# main.net
KiCad netlist of a schematic drawn in Altium Designer
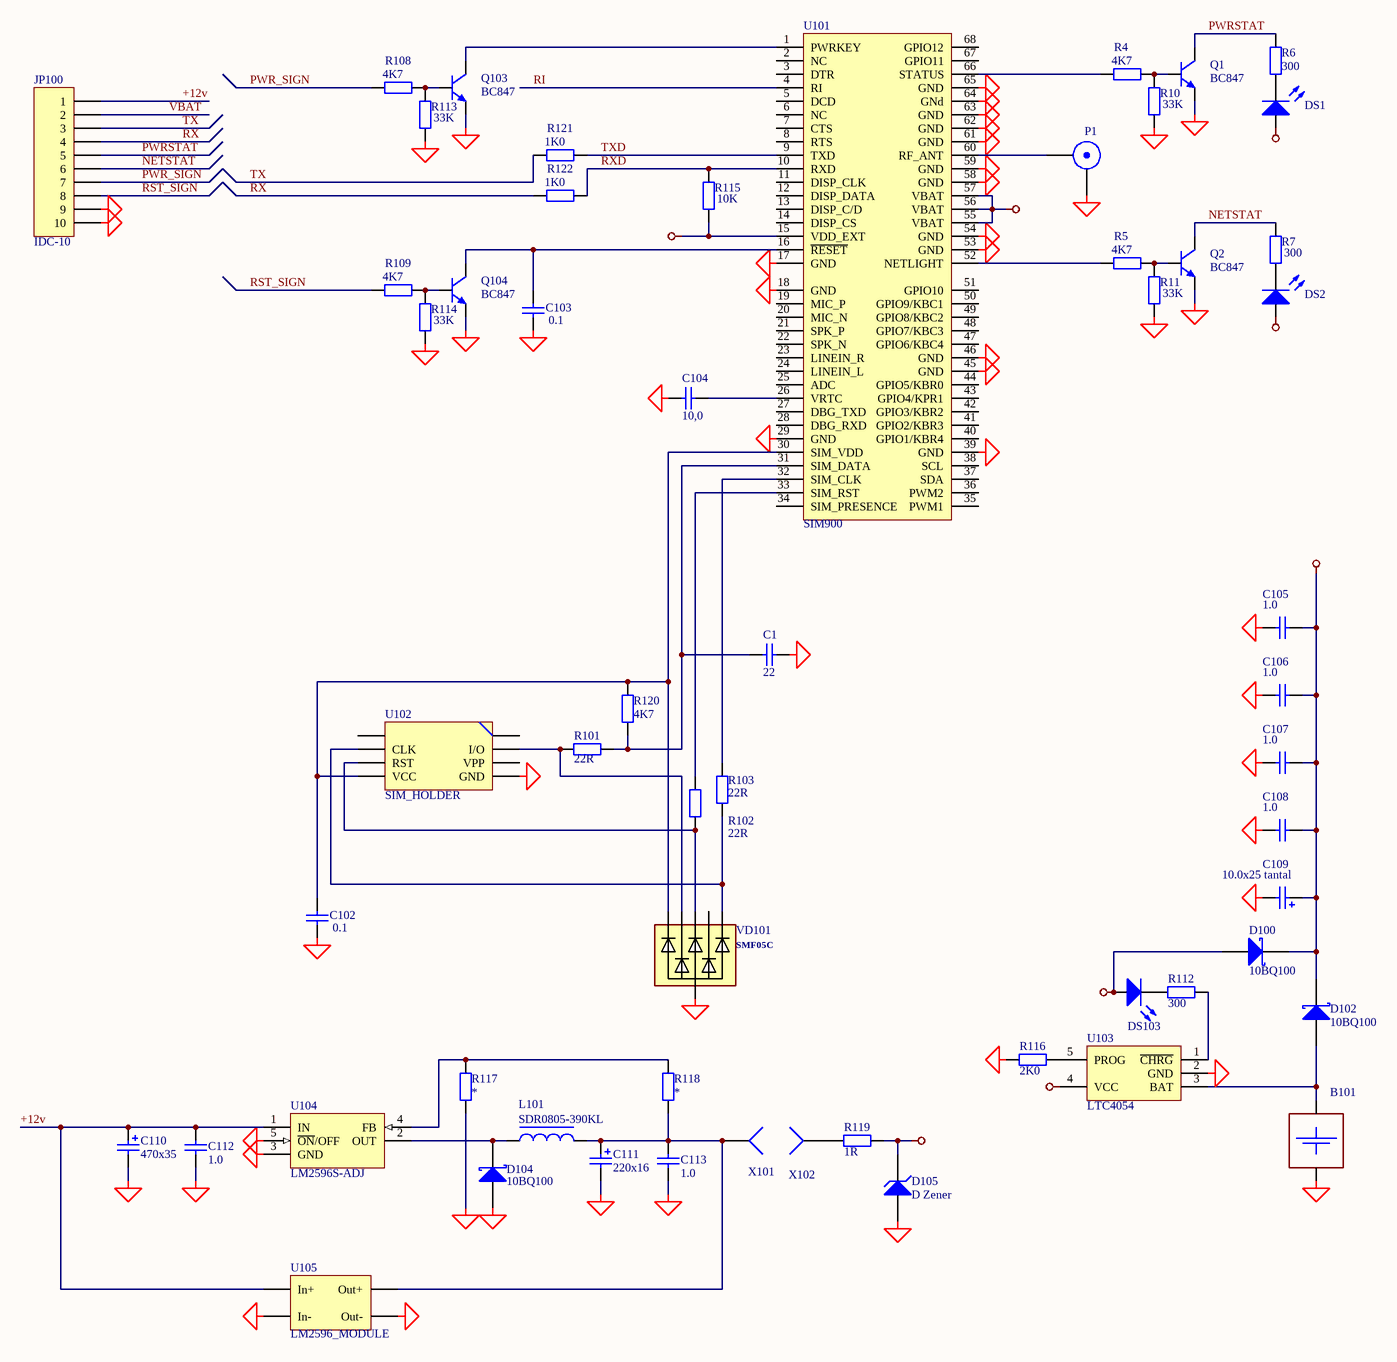
[diagram p0: main.SchDoc]

(export (version "E")
  (design (tool "Eeschema 10.0.6"))
  (components
    (comp (ref "B101")
      (value "BAT18650_HOLDER")
      (footprint "BAT18650_HOLDER")
      (libsource (lib "PAL") (part "BAT18650_HOLDER"))
    )
    (comp (ref "C1")
      (value "22")
      (footprint "_1206")
      (description "Capacitor")
      (fields (field (name "MANUFACTURER") "Generic Components") (field (name "PUBLISHER") "Altium Limited"))
      (libsource (lib "Miscellaneous Devices") (part "Cap Semi"))
    )
    (comp (ref "C102")
      (value "0.1")
      (footprint "_1206")
      (description "Capacitor")
      (fields (field (name "MANUFACTURER") "Generic Components") (field (name "PUBLISHER") "Altium Limited"))
      (libsource (lib "Miscellaneous Devices") (part "Cap Semi"))
    )
    (comp (ref "C103")
      (value "0.1")
      (footprint "_1206")
      (description "Capacitor")
      (fields (field (name "MANUFACTURER") "Generic Components") (field (name "PUBLISHER") "Altium Limited"))
      (libsource (lib "Miscellaneous Devices") (part "Cap Semi"))
    )
    (comp (ref "C104")
      (value "10,0")
      (footprint "_1206")
      (description "Capacitor")
      (fields (field (name "MANUFACTURER") "Generic Components") (field (name "PUBLISHER") "Altium Limited"))
      (libsource (lib "Miscellaneous Devices") (part "Cap Semi"))
    )
    (comp (ref "C105")
      (value "1.0")
      (footprint "_1206")
      (description "Capacitor")
      (fields (field (name "MANUFACTURER") "Generic Components") (field (name "PUBLISHER") "Altium Limited"))
      (libsource (lib "Miscellaneous Devices") (part "Cap Semi"))
    )
    (comp (ref "C106")
      (value "1.0")
      (footprint "_1206")
      (description "Capacitor")
      (fields (field (name "MANUFACTURER") "Generic Components") (field (name "PUBLISHER") "Altium Limited"))
      (libsource (lib "Miscellaneous Devices") (part "Cap Semi"))
    )
    (comp (ref "C107")
      (value "1.0")
      (footprint "_1206")
      (description "Capacitor")
      (fields (field (name "MANUFACTURER") "Generic Components") (field (name "PUBLISHER") "Altium Limited"))
      (libsource (lib "Miscellaneous Devices") (part "Cap Semi"))
    )
    (comp (ref "C108")
      (value "1.0")
      (footprint "_1206")
      (description "Capacitor")
      (fields (field (name "MANUFACTURER") "Generic Components") (field (name "PUBLISHER") "Altium Limited"))
      (libsource (lib "Miscellaneous Devices") (part "Cap Semi"))
    )
    (comp (ref "C109")
      (value "10.0x25 tantal")
      (footprint "CAP_EL_6_3")
      (description "Polarized Capacitor (Radial)")
      (fields (field (name "MANUFACTURER") "Generic Components") (field (name "PUBLISHER") "Altium Limited"))
      (libsource (lib "PAL") (part "Cap Pol1"))
    )
    (comp (ref "C110")
      (value "470x35")
      (footprint "el5")
      (description "Polarized Capacitor (Radial)")
      (fields (field (name "MANUFACTURER") "Generic Components") (field (name "PUBLISHER") "Altium Limited"))
      (libsource (lib "BUF") (part "Cap Pol"))
    )
    (comp (ref "C111")
      (value "220x16")
      (footprint "el3")
      (description "Polarized Capacitor (Radial)")
      (fields (field (name "MANUFACTURER") "Generic Components") (field (name "PUBLISHER") "Altium Limited"))
      (libsource (lib "BUF") (part "Cap Pol"))
    )
    (comp (ref "C112")
      (value "Cap")
      (footprint "_1206")
      (description "Capacitor")
      (fields
        (field (name "MANUFACTURER") "Generic Components")
        (field (name "ALTIUM_VALUE") "1.0")
        (field (name "PUBLISHER") "Altium Limited")
      )
      (libsource (lib "BUF") (part "Cap"))
    )
    (comp (ref "C113")
      (value "Cap")
      (footprint "_1206")
      (description "Capacitor")
      (fields
        (field (name "MANUFACTURER") "Generic Components")
        (field (name "ALTIUM_VALUE") "1.0")
        (field (name "PUBLISHER") "Altium Limited")
      )
      (libsource (lib "BUF") (part "Cap"))
    )
    (comp (ref "D100")
      (value "10BQ100")
      (footprint "DSO-C2/X2.3")
      (description "Schottky Rectifier")
      (fields
        (field (name "MANUFACTURER") "International Rectifier")
        (field (name "PUBLISHER") "Altium Limited")
      )
      (libsource (lib "IR Discrete Diode") (part "10BQ015"))
    )
    (comp (ref "D102")
      (value "10BQ100")
      (footprint "DSO-C2/X2.3")
      (description "Schottky Rectifier")
      (fields
        (field (name "MANUFACTURER") "International Rectifier")
        (field (name "PUBLISHER") "Altium Limited")
      )
      (libsource (lib "IR Discrete Diode") (part "10BQ015"))
    )
    (comp (ref "D104")
      (value "10BQ100")
      (footprint "DSO-C2/X2.3")
      (description "Schottky Rectifier")
      (fields
        (field (name "MANUFACTURER") "International Rectifier")
        (field (name "PUBLISHER") "Altium Limited")
      )
      (libsource (lib "IR Discrete Diode") (part "10BQ015"))
    )
    (comp (ref "D105")
      (value "D Zener")
      (footprint "_1206d")
      (description "Zener Diode")
      (fields (field (name "MANUFACTURER") "Generic Components") (field (name "PUBLISHER") "Altium Limited"))
      (libsource (lib "Miscellaneous Devices") (part "D Zener"))
    )
    (comp (ref "DS1")
      (value "LED0")
      (footprint "el3")
      (description "Typical INFRARED GaAs LED")
      (fields (field (name "MANUFACTURER") "Generic Components") (field (name "PUBLISHER") "Altium Limited"))
      (libsource (lib "PAL") (part "LED0"))
    )
    (comp (ref "DS2")
      (value "LED0")
      (footprint "el3")
      (description "Typical INFRARED GaAs LED")
      (fields (field (name "MANUFACTURER") "Generic Components") (field (name "PUBLISHER") "Altium Limited"))
      (libsource (lib "PAL") (part "LED0"))
    )
    (comp (ref "DS103")
      (value "LED0")
      (footprint "el3")
      (description "Typical INFRARED GaAs LED")
      (fields (field (name "MANUFACTURER") "Generic Components") (field (name "PUBLISHER") "Altium Limited"))
      (libsource (lib "") (part "LED0_1"))
    )
    (comp (ref "JP100")
      (value "IDC-10")
      (footprint "HDR2X5")
      (description "Header, 10-Pin")
      (fields (field (name "MANUFACTURER") "Generic Components") (field (name "PUBLISHER") "Altium Limited"))
      (libsource (lib "Miscellaneous Connectors") (part "Header 10"))
    )
    (comp (ref "L101")
      (value "SDR0805-390KL")
      (footprint "L10x10")
      (description "Magnetic-Core Inductor")
      (fields (field (name "MANUFACTURER") "Generic Components") (field (name "PUBLISHER") "Altium Limited"))
      (libsource (lib "PAL") (part "Inductor Konstr 2"))
    )
    (comp (ref "P1")
      (value "SMB")
      (footprint "SMB_V-RJ45")
      (description "SMB Straight Connector")
      (fields (field (name "MANUFACTURER") "Generic Components") (field (name "PUBLISHER") "Altium Limited"))
      (libsource (lib "Miscellaneous Connectors") (part "SMB"))
    )
    (comp (ref "Q1")
      (value "BC847")
      (footprint "SO-G3/C2.5")
      (description "General Purpose Transistor NPN Silicon")
      (fields (field (name "MANUFACTURER") "Motorola") (field (name "PUBLISHER") "Altium Limited"))
      (libsource (lib "PAL") (part "BC847ALT1"))
    )
    (comp (ref "Q2")
      (value "BC847")
      (footprint "SO-G3/C2.5")
      (description "General Purpose Transistor NPN Silicon")
      (fields (field (name "MANUFACTURER") "Motorola") (field (name "PUBLISHER") "Altium Limited"))
      (libsource (lib "PAL") (part "BC847ALT1"))
    )
    (comp (ref "Q103")
      (value "BC847")
      (footprint "SO-G3/C2.5")
      (description "General Purpose Transistor NPN Silicon")
      (fields (field (name "MANUFACTURER") "Motorola") (field (name "PUBLISHER") "Altium Limited"))
      (libsource (lib "PAL") (part "BC847ALT1"))
    )
    (comp (ref "Q104")
      (value "BC847")
      (footprint "SO-G3/C2.5")
      (description "General Purpose Transistor NPN Silicon")
      (fields (field (name "MANUFACTURER") "Motorola") (field (name "PUBLISHER") "Altium Limited"))
      (libsource (lib "PAL") (part "BC847ALT1"))
    )
    (comp (ref "R4")
      (value "4K7")
      (footprint "_1206")
      (description "Resistor")
      (fields (field (name "MANUFACTURER") "Generic Components") (field (name "PUBLISHER") "Altium Limited"))
      (libsource (lib "Miscellaneous Devices") (part "Res2"))
    )
    (comp (ref "R5")
      (value "4K7")
      (footprint "_1206")
      (description "Resistor")
      (fields (field (name "MANUFACTURER") "Generic Components") (field (name "PUBLISHER") "Altium Limited"))
      (libsource (lib "Miscellaneous Devices") (part "Res2"))
    )
    (comp (ref "R6")
      (value "300")
      (footprint "_1206")
      (description "Resistor")
      (fields (field (name "MANUFACTURER") "Generic Components") (field (name "PUBLISHER") "Altium Limited"))
      (libsource (lib "") (part "Res2_3"))
    )
    (comp (ref "R7")
      (value "300")
      (footprint "_1206")
      (description "Resistor")
      (fields (field (name "MANUFACTURER") "Generic Components") (field (name "PUBLISHER") "Altium Limited"))
      (libsource (lib "") (part "Res2_2"))
    )
    (comp (ref "R10")
      (value "33K")
      (footprint "_1206")
      (description "Resistor")
      (fields (field (name "MANUFACTURER") "Generic Components") (field (name "PUBLISHER") "Altium Limited"))
      (libsource (lib "") (part "Res2_2"))
    )
    (comp (ref "R11")
      (value "33K")
      (footprint "_1206")
      (description "Resistor")
      (fields (field (name "MANUFACTURER") "Generic Components") (field (name "PUBLISHER") "Altium Limited"))
      (libsource (lib "") (part "Res2_2"))
    )
    (comp (ref "R101")
      (value "22R")
      (footprint "_1206")
      (description "Resistor")
      (fields (field (name "MANUFACTURER") "Generic Components") (field (name "PUBLISHER") "Altium Limited"))
      (libsource (lib "") (part "Res2_2"))
    )
    (comp (ref "R102")
      (value "22R")
      (footprint "_1206")
      (description "Resistor")
      (fields (field (name "MANUFACTURER") "Generic Components") (field (name "PUBLISHER") "Altium Limited"))
      (libsource (lib "Miscellaneous Devices") (part "Res2"))
    )
    (comp (ref "R103")
      (value "22R")
      (footprint "_1206")
      (description "Resistor")
      (fields (field (name "MANUFACTURER") "Generic Components") (field (name "PUBLISHER") "Altium Limited"))
      (libsource (lib "Miscellaneous Devices") (part "Res2"))
    )
    (comp (ref "R108")
      (value "4K7")
      (footprint "_1206")
      (description "Resistor")
      (fields (field (name "MANUFACTURER") "Generic Components") (field (name "PUBLISHER") "Altium Limited"))
      (libsource (lib "Miscellaneous Devices") (part "Res2"))
    )
    (comp (ref "R109")
      (value "4K7")
      (footprint "_1206")
      (description "Resistor")
      (fields (field (name "MANUFACTURER") "Generic Components") (field (name "PUBLISHER") "Altium Limited"))
      (libsource (lib "Miscellaneous Devices") (part "Res2"))
    )
    (comp (ref "R112")
      (value "300")
      (footprint "_1206")
      (description "Resistor")
      (fields (field (name "MANUFACTURER") "Generic Components") (field (name "PUBLISHER") "Altium Limited"))
      (libsource (lib "") (part "Res2_1"))
    )
    (comp (ref "R113")
      (value "33K")
      (footprint "_1206")
      (description "Resistor")
      (fields (field (name "MANUFACTURER") "Generic Components") (field (name "PUBLISHER") "Altium Limited"))
      (libsource (lib "") (part "Res2_2"))
    )
    (comp (ref "R114")
      (value "33K")
      (footprint "_1206")
      (description "Resistor")
      (fields (field (name "MANUFACTURER") "Generic Components") (field (name "PUBLISHER") "Altium Limited"))
      (libsource (lib "") (part "Res2_2"))
    )
    (comp (ref "R115")
      (value "10K")
      (footprint "_1206")
      (description "Resistor")
      (fields (field (name "MANUFACTURER") "Generic Components") (field (name "PUBLISHER") "Altium Limited"))
      (libsource (lib "") (part "Res2_2"))
    )
    (comp (ref "R116")
      (value "2K0")
      (footprint "_1206")
      (description "Resistor")
      (fields (field (name "MANUFACTURER") "Generic Components") (field (name "PUBLISHER") "Altium Limited"))
      (libsource (lib "") (part "Res2_1"))
    )
    (comp (ref "R117")
      (value "*")
      (footprint "_1206")
      (description "Resistor")
      (fields (field (name "MANUFACTURER") "Generic Components") (field (name "PUBLISHER") "Altium Limited"))
      (libsource (lib "Miscellaneous Devices") (part "Res2"))
    )
    (comp (ref "R118")
      (value "*")
      (footprint "_1206")
      (description "Resistor")
      (fields (field (name "MANUFACTURER") "Generic Components") (field (name "PUBLISHER") "Altium Limited"))
      (libsource (lib "Miscellaneous Devices") (part "Res2"))
    )
    (comp (ref "R119")
      (value "1R")
      (footprint "_1206")
      (description "Resistor")
      (fields (field (name "MANUFACTURER") "Generic Components") (field (name "PUBLISHER") "Altium Limited"))
      (libsource (lib "") (part "Res2_3"))
    )
    (comp (ref "R120")
      (value "4K7")
      (footprint "_1206")
      (description "Resistor")
      (fields (field (name "MANUFACTURER") "Generic Components") (field (name "PUBLISHER") "Altium Limited"))
      (libsource (lib "Miscellaneous Devices") (part "Res2"))
    )
    (comp (ref "R121")
      (value "1K0")
      (footprint "_1206")
      (description "Resistor")
      (fields (field (name "MANUFACTURER") "Generic Components") (field (name "PUBLISHER") "Altium Limited"))
      (libsource (lib "Miscellaneous Devices") (part "Res2"))
    )
    (comp (ref "R122")
      (value "1K0")
      (footprint "_1206")
      (description "Resistor")
      (fields (field (name "MANUFACTURER") "Generic Components") (field (name "PUBLISHER") "Altium Limited"))
      (libsource (lib "Miscellaneous Devices") (part "Res2"))
    )
    (comp (ref "U101") (value "SIM900") (footprint "SIM900F") (libsource (lib "Schlib1") (part "SIM900")))
    (comp (ref "U102")
      (value "SIM_HOLDER")
      (footprint "SIM_HOLDER_1")
      (libsource (lib "Schlib1") (part "SIM_HOLDER"))
    )
    (comp (ref "U103") (value "LTC4054") (footprint "SO-G5/P.95") (libsource (lib "PAL") (part "LTC4054")))
    (comp (ref "U104")
      (value "LM2596S-ADJ")
      (footprint "SIP-G5/Y2.1")
      (description "Simple Switcher Power Converter 150 kHz 3A Step Down Voltage Regulator")
      (fields
        (field (name "MANUFACTURER") "National Semiconductor")
        (field (name "PUBLISHER") "Altium Limited")
      )
      (libsource (lib "NSC Power Mgt Switching Regulator") (part "LM2596S-ADJ"))
    )
    (comp (ref "U105")
      (value "LM2596_MODULE")
      (footprint "LM2596_MODULE_1")
      (libsource (lib "PAL") (part "LM2596_MODULE"))
    )
    (comp (ref "VD101")
      (value "*")
      (footprint "sot363")
      (fields (field (name "MANUFACTURERPARTNUMBER") "SMF05C"))
      (libsource (lib "PAL") (part "SMF05C"))
    )
    (comp (ref "X101")
      (value "Socket")
      (footprint "PIN1")
      (fields (field (name "MANUFACTURER") "Generic Components") (field (name "PUBLISHER") "Altium Limited"))
      (libsource (lib "Miscellaneous Connectors") (part "Socket"))
    )
    (comp (ref "X102")
      (value "Socket")
      (footprint "PIN1")
      (fields (field (name "MANUFACTURER") "Generic Components") (field (name "PUBLISHER") "Altium Limited"))
      (libsource (lib "Miscellaneous Connectors") (part "Socket"))
    )
  )
  (nets
    (net (code "1") (name "+5v") (class "Default")
      (node (ref "D100") (pin "1") (pinfunction "A_1") (pintype "passive"))
      (node (ref "D105") (pin "2") (pinfunction "K_2") (pintype "passive"))
      (node (ref "DS103") (pin "1") (pinfunction "A_1") (pintype "passive"))
      (node (ref "R119") (pin "2") (pinfunction "2_2") (pintype "passive"))
      (node (ref "U103") (pin "4") (pinfunction "VCC_4") (pintype "passive"))
    )
    (net (code "2") (name "/+12v") (class "Default")
      (node (ref "C110") (pin "1") (pinfunction "1_1") (pintype "passive"))
      (node (ref "C112") (pin "2") (pinfunction "2_2") (pintype "passive"))
      (node (ref "JP100") (pin "1") (pinfunction "1_1") (pintype "passive"))
      (node (ref "U104") (pin "1") (pinfunction "IN_1") (pintype "power_in"))
      (node (ref "U105") (pin "1") (pinfunction "In+_1") (pintype "passive"))
    )
    (net (code "3") (name "/NETSTAT") (class "Default")
      (node (ref "JP100") (pin "6") (pinfunction "6_6") (pintype "passive"))
      (node (ref "Q2") (pin "3") (pinfunction "C_3") (pintype "passive"))
      (node (ref "R7") (pin "1") (pinfunction "1_1") (pintype "passive"))
    )
    (net (code "4") (name "/PWRSTAT") (class "Default")
      (node (ref "JP100") (pin "5") (pinfunction "5_5") (pintype "passive"))
      (node (ref "Q1") (pin "3") (pinfunction "C_3") (pintype "passive"))
      (node (ref "R6") (pin "2") (pinfunction "2_2") (pintype "passive"))
    )
    (net (code "5") (name "/PWR_SIGN") (class "Default")
      (node (ref "JP100") (pin "7") (pinfunction "7_7") (pintype "passive"))
      (node (ref "R108") (pin "2") (pinfunction "2_2") (pintype "passive"))
    )
    (net (code "6") (name "/RI") (class "Default")
      (node (ref "U101") (pin "4") (pinfunction "RI_4") (pintype "passive"))
    )
    (net (code "7") (name "/RST_SIGN") (class "Default")
      (node (ref "JP100") (pin "8") (pinfunction "8_8") (pintype "passive"))
      (node (ref "R109") (pin "2") (pinfunction "2_2") (pintype "passive"))
    )
    (net (code "8") (name "/RX") (class "Default")
      (node (ref "JP100") (pin "4") (pinfunction "4_4") (pintype "passive"))
      (node (ref "R122") (pin "2") (pinfunction "2_2") (pintype "passive"))
    )
    (net (code "9") (name "/RXD") (class "Default")
      (node (ref "R115") (pin "1") (pinfunction "1_1") (pintype "passive"))
      (node (ref "R122") (pin "1") (pinfunction "1_1") (pintype "passive"))
      (node (ref "U101") (pin "10") (pinfunction "RXD_10") (pintype "passive"))
    )
    (net (code "10") (name "/TX") (class "Default")
      (node (ref "JP100") (pin "3") (pinfunction "3_3") (pintype "passive"))
      (node (ref "R121") (pin "2") (pinfunction "2_2") (pintype "passive"))
    )
    (net (code "11") (name "/TXD") (class "Default")
      (node (ref "R121") (pin "1") (pinfunction "1_1") (pintype "passive"))
      (node (ref "U101") (pin "9") (pinfunction "TXD_9") (pintype "passive"))
    )
    (net (code "12") (name "GND") (class "Default")
      (node (ref "B101") (pin "2") (pinfunction "-_2") (pintype "passive"))
      (node (ref "C1") (pin "1") (pinfunction "1_1") (pintype "passive"))
      (node (ref "C102") (pin "1") (pinfunction "1_1") (pintype "passive"))
      (node (ref "C103") (pin "1") (pinfunction "1_1") (pintype "passive"))
      (node (ref "C104") (pin "2") (pinfunction "2_2") (pintype "passive"))
      (node (ref "C105") (pin "1") (pinfunction "1_1") (pintype "passive"))
      (node (ref "C106") (pin "1") (pinfunction "1_1") (pintype "passive"))
      (node (ref "C107") (pin "1") (pinfunction "1_1") (pintype "passive"))
      (node (ref "C108") (pin "1") (pinfunction "1_1") (pintype "passive"))
      (node (ref "C109") (pin "2") (pinfunction "2_2") (pintype "passive"))
      (node (ref "C110") (pin "2") (pinfunction "2_2") (pintype "passive"))
      (node (ref "C111") (pin "2") (pinfunction "2_2") (pintype "passive"))
      (node (ref "C112") (pin "1") (pinfunction "1_1") (pintype "passive"))
      (node (ref "C113") (pin "1") (pinfunction "1_1") (pintype "passive"))
      (node (ref "D104") (pin "1") (pinfunction "A_1") (pintype "passive"))
      (node (ref "D105") (pin "1") (pinfunction "A_1") (pintype "passive"))
      (node (ref "JP100") (pin "10") (pinfunction "10_10") (pintype "passive"))
      (node (ref "JP100") (pin "9") (pinfunction "9_9") (pintype "passive"))
      (node (ref "P1") (pin "2") (pinfunction "Y_2") (pintype "passive"))
      (node (ref "Q1") (pin "2") (pinfunction "E_2") (pintype "passive"))
      (node (ref "Q103") (pin "2") (pinfunction "E_2") (pintype "passive"))
      (node (ref "Q104") (pin "2") (pinfunction "E_2") (pintype "passive"))
      (node (ref "Q2") (pin "2") (pinfunction "E_2") (pintype "passive"))
      (node (ref "R10") (pin "2") (pinfunction "2_2") (pintype "passive"))
      (node (ref "R11") (pin "2") (pinfunction "2_2") (pintype "passive"))
      (node (ref "R113") (pin "2") (pinfunction "2_2") (pintype "passive"))
      (node (ref "R114") (pin "2") (pinfunction "2_2") (pintype "passive"))
      (node (ref "R116") (pin "2") (pinfunction "2_2") (pintype "passive"))
      (node (ref "R117") (pin "2") (pinfunction "2_2") (pintype "passive"))
      (node (ref "U101") (pin "17") (pinfunction "GND_17") (pintype "passive"))
      (node (ref "U101") (pin "18") (pinfunction "GND_18") (pintype "passive"))
      (node (ref "U101") (pin "29") (pinfunction "GND_29") (pintype "passive"))
      (node (ref "U101") (pin "39") (pinfunction "GND_39") (pintype "passive"))
      (node (ref "U101") (pin "45") (pinfunction "GND_45") (pintype "passive"))
      (node (ref "U101") (pin "46") (pinfunction "GND_46") (pintype "passive"))
      (node (ref "U101") (pin "53") (pinfunction "GND_53") (pintype "passive"))
      (node (ref "U101") (pin "54") (pinfunction "GND_54") (pintype "passive"))
      (node (ref "U101") (pin "58") (pinfunction "GND_58") (pintype "passive"))
      (node (ref "U101") (pin "59") (pinfunction "GND_59") (pintype "passive"))
      (node (ref "U101") (pin "61") (pinfunction "GND_61") (pintype "passive"))
      (node (ref "U101") (pin "62") (pinfunction "GND_62") (pintype "passive"))
      (node (ref "U101") (pin "63") (pinfunction "GND_63") (pintype "passive"))
      (node (ref "U101") (pin "64") (pinfunction "GNd_64") (pintype "passive"))
      (node (ref "U101") (pin "65") (pinfunction "GND_65") (pintype "passive"))
      (node (ref "U102") (pin "5") (pinfunction "GND_5") (pintype "passive"))
      (node (ref "U103") (pin "2") (pinfunction "GND_2") (pintype "passive"))
      (node (ref "U104") (pin "3") (pinfunction "GND_3") (pintype "power_in"))
      (node (ref "U104") (pin "5") (pinfunction "~{ON}/OFF_5") (pintype "input"))
      (node (ref "U105") (pin "2") (pinfunction "In-_2") (pintype "passive"))
      (node (ref "U105") (pin "3") (pinfunction "Out-_3") (pintype "passive"))
      (node (ref "VD101") (pin "2") (pinfunction "2_2") (pintype "passive"))
    )
    (net (code "13") (name "Net-(B101-+)") (class "Default")
      (node (ref "B101") (pin "1") (pinfunction "+_1") (pintype "passive"))
      (node (ref "D102") (pin "1") (pinfunction "A_1") (pintype "passive"))
      (node (ref "U103") (pin "3") (pinfunction "BAT_3") (pintype "passive"))
    )
    (net (code "14") (name "Net-(D104-K)") (class "Default")
      (node (ref "D104") (pin "2") (pinfunction "K_2") (pintype "passive"))
      (node (ref "L101") (pin "1") (pinfunction "1_1") (pintype "passive"))
      (node (ref "U104") (pin "2") (pinfunction "OUT_2") (pintype "power_in"))
    )
    (net (code "15") (name "Net-(DS1-K)") (class "Default")
      (node (ref "DS1") (pin "2") (pinfunction "K_2") (pintype "passive"))
      (node (ref "R6") (pin "1") (pinfunction "1_1") (pintype "passive"))
    )
    (net (code "16") (name "Net-(DS2-K)") (class "Default")
      (node (ref "DS2") (pin "2") (pinfunction "K_2") (pintype "passive"))
      (node (ref "R7") (pin "2") (pinfunction "2_2") (pintype "passive"))
    )
    (net (code "17") (name "Net-(DS103-K)") (class "Default")
      (node (ref "DS103") (pin "2") (pinfunction "K_2") (pintype "passive"))
      (node (ref "R112") (pin "2") (pinfunction "2_2") (pintype "passive"))
    )
    (net (code "18") (name "Net-(P1-X)") (class "Default")
      (node (ref "P1") (pin "1") (pinfunction "X_1") (pintype "passive"))
      (node (ref "U101") (pin "60") (pinfunction "RF_ANT_60") (pintype "passive"))
    )
    (net (code "19") (name "Net-(Q1-B)") (class "Default")
      (node (ref "Q1") (pin "1") (pinfunction "B_1") (pintype "passive"))
      (node (ref "R10") (pin "1") (pinfunction "1_1") (pintype "passive"))
      (node (ref "R4") (pin "1") (pinfunction "1_1") (pintype "passive"))
    )
    (net (code "20") (name "Net-(Q2-B)") (class "Default")
      (node (ref "Q2") (pin "1") (pinfunction "B_1") (pintype "passive"))
      (node (ref "R11") (pin "1") (pinfunction "1_1") (pintype "passive"))
      (node (ref "R5") (pin "1") (pinfunction "1_1") (pintype "passive"))
    )
    (net (code "21") (name "Net-(Q103-B)") (class "Default")
      (node (ref "Q103") (pin "1") (pinfunction "B_1") (pintype "passive"))
      (node (ref "R108") (pin "1") (pinfunction "1_1") (pintype "passive"))
      (node (ref "R113") (pin "1") (pinfunction "1_1") (pintype "passive"))
    )
    (net (code "22") (name "Net-(Q103-C)") (class "Default")
      (node (ref "Q103") (pin "3") (pinfunction "C_3") (pintype "passive"))
      (node (ref "U101") (pin "1") (pinfunction "PWRKEY_1") (pintype "passive"))
    )
    (net (code "23") (name "Net-(Q104-B)") (class "Default")
      (node (ref "Q104") (pin "1") (pinfunction "B_1") (pintype "passive"))
      (node (ref "R109") (pin "1") (pinfunction "1_1") (pintype "passive"))
      (node (ref "R114") (pin "1") (pinfunction "1_1") (pintype "passive"))
    )
    (net (code "24") (name "Net-(Q104-C)") (class "Default")
      (node (ref "C103") (pin "2") (pinfunction "2_2") (pintype "passive"))
      (node (ref "Q104") (pin "3") (pinfunction "C_3") (pintype "passive"))
      (node (ref "U101") (pin "16") (pinfunction "~{RESET}_16") (pintype "passive"))
    )
    (net (code "25") (name "Net-(R119-Pad1)") (class "Default")
      (node (ref "R119") (pin "1") (pinfunction "1_1") (pintype "passive"))
      (node (ref "X102") (pin "1") (pinfunction "1_1") (pintype "passive"))
    )
    (net (code "26") (name "Net-(U101-NETLIGHT)") (class "Default")
      (node (ref "R5") (pin "2") (pinfunction "2_2") (pintype "passive"))
      (node (ref "U101") (pin "52") (pinfunction "NETLIGHT_52") (pintype "passive"))
    )
    (net (code "27") (name "Net-(U101-SIM_CLK)") (class "Default")
      (node (ref "R103") (pin "1") (pinfunction "1_1") (pintype "passive"))
      (node (ref "U101") (pin "32") (pinfunction "SIM_CLK_32") (pintype "passive"))
    )
    (net (code "28") (name "Net-(U101-SIM_DATA)") (class "Default")
      (node (ref "C1") (pin "2") (pinfunction "2_2") (pintype "passive"))
      (node (ref "R101") (pin "1") (pinfunction "1_1") (pintype "passive"))
      (node (ref "R120") (pin "2") (pinfunction "2_2") (pintype "passive"))
      (node (ref "U101") (pin "31") (pinfunction "SIM_DATA_31") (pintype "passive"))
    )
    (net (code "29") (name "Net-(U101-SIM_RST)") (class "Default")
      (node (ref "R102") (pin "1") (pinfunction "1_1") (pintype "passive"))
      (node (ref "U101") (pin "33") (pinfunction "SIM_RST_33") (pintype "passive"))
    )
    (net (code "30") (name "Net-(U101-SIM_VDD)") (class "Default")
      (node (ref "C102") (pin "2") (pinfunction "2_2") (pintype "passive"))
      (node (ref "R120") (pin "1") (pinfunction "1_1") (pintype "passive"))
      (node (ref "U101") (pin "30") (pinfunction "SIM_VDD_30") (pintype "passive"))
      (node (ref "U102") (pin "4") (pinfunction "VCC_4") (pintype "passive"))
      (node (ref "VD101") (pin "1") (pinfunction "1_1") (pintype "passive"))
    )
    (net (code "31") (name "Net-(U101-STATUS)") (class "Default")
      (node (ref "R4") (pin "2") (pinfunction "2_2") (pintype "passive"))
      (node (ref "U101") (pin "66") (pinfunction "STATUS_66") (pintype "passive"))
    )
    (net (code "32") (name "Net-(U101-VRTC)") (class "Default")
      (node (ref "C104") (pin "1") (pinfunction "1_1") (pintype "passive"))
      (node (ref "U101") (pin "26") (pinfunction "VRTC_26") (pintype "passive"))
    )
    (net (code "33") (name "Net-(U102-CLK)") (class "Default")
      (node (ref "R103") (pin "2") (pinfunction "2_2") (pintype "passive"))
      (node (ref "U102") (pin "2") (pinfunction "CLK_2") (pintype "passive"))
      (node (ref "VD101") (pin "6") (pinfunction "6_6") (pintype "passive"))
    )
    (net (code "34") (name "Net-(U102-I{slash}O)") (class "Default")
      (node (ref "R101") (pin "2") (pinfunction "2_2") (pintype "passive"))
      (node (ref "U102") (pin "7") (pinfunction "I/O_7") (pintype "passive"))
      (node (ref "VD101") (pin "3") (pinfunction "3_3") (pintype "passive"))
    )
    (net (code "35") (name "Net-(U102-RST)") (class "Default")
      (node (ref "R102") (pin "2") (pinfunction "2_2") (pintype "passive"))
      (node (ref "U102") (pin "3") (pinfunction "RST_3") (pintype "passive"))
      (node (ref "VD101") (pin "4") (pinfunction "4_4") (pintype "passive"))
    )
    (net (code "36") (name "Net-(U103-PROG)") (class "Default")
      (node (ref "R116") (pin "1") (pinfunction "1_1") (pintype "passive"))
      (node (ref "U103") (pin "5") (pinfunction "PROG_5") (pintype "passive"))
    )
    (net (code "37") (name "Net-(U103-~{CHRG})") (class "Default")
      (node (ref "R112") (pin "1") (pinfunction "1_1") (pintype "passive"))
      (node (ref "U103") (pin "1") (pinfunction "~{CHRG}_1") (pintype "passive"))
    )
    (net (code "38") (name "Net-(U104-FB)") (class "Default")
      (node (ref "R117") (pin "1") (pinfunction "1_1") (pintype "passive"))
      (node (ref "R118") (pin "1") (pinfunction "1_1") (pintype "passive"))
      (node (ref "U104") (pin "4") (pinfunction "FB_4") (pintype "input"))
    )
    (net (code "39") (name "Net-(U105-Out+)") (class "Default")
      (node (ref "C111") (pin "1") (pinfunction "1_1") (pintype "passive"))
      (node (ref "C113") (pin "2") (pinfunction "2_2") (pintype "passive"))
      (node (ref "L101") (pin "2") (pinfunction "2_2") (pintype "passive"))
      (node (ref "R118") (pin "2") (pinfunction "2_2") (pintype "passive"))
      (node (ref "U105") (pin "4") (pinfunction "Out+_4") (pintype "passive"))
      (node (ref "X101") (pin "1") (pinfunction "1_1") (pintype "passive"))
    )
    (net (code "40") (name "VBAT") (class "Default")
      (node (ref "C105") (pin "2") (pinfunction "2_2") (pintype "passive"))
      (node (ref "C106") (pin "2") (pinfunction "2_2") (pintype "passive"))
      (node (ref "C107") (pin "2") (pinfunction "2_2") (pintype "passive"))
      (node (ref "C108") (pin "2") (pinfunction "2_2") (pintype "passive"))
      (node (ref "C109") (pin "1") (pinfunction "1_1") (pintype "passive"))
      (node (ref "D100") (pin "2") (pinfunction "K_2") (pintype "passive"))
      (node (ref "D102") (pin "2") (pinfunction "K_2") (pintype "passive"))
      (node (ref "DS1") (pin "1") (pinfunction "A_1") (pintype "passive"))
      (node (ref "DS2") (pin "1") (pinfunction "A_1") (pintype "passive"))
      (node (ref "JP100") (pin "2") (pinfunction "2_2") (pintype "passive"))
      (node (ref "U101") (pin "55") (pinfunction "VBAT_55") (pintype "passive"))
      (node (ref "U101") (pin "56") (pinfunction "VBAT_56") (pintype "passive"))
      (node (ref "U101") (pin "57") (pinfunction "VBAT_57") (pintype "passive"))
    )
    (net (code "41") (name "VDD_EXT") (class "Default")
      (node (ref "R115") (pin "2") (pinfunction "2_2") (pintype "passive"))
      (node (ref "U101") (pin "15") (pinfunction "VDD_EXT_15") (pintype "passive"))
    )
    (net (code "42") (name "unconnected-(U101-ADC-Pad25)") (class "Default")
      (node (ref "U101") (pin "25") (pinfunction "ADC_25") (pintype "passive"))
    )
    (net (code "43") (name "unconnected-(U101-CTS-Pad7)") (class "Default")
      (node (ref "U101") (pin "7") (pinfunction "CTS_7") (pintype "passive"))
    )
    (net (code "44") (name "unconnected-(U101-DBG_RXD-Pad28)") (class "Default")
      (node (ref "U101") (pin "28") (pinfunction "DBG_RXD_28") (pintype "passive"))
    )
    (net (code "45") (name "unconnected-(U101-DBG_TXD-Pad27)") (class "Default")
      (node (ref "U101") (pin "27") (pinfunction "DBG_TXD_27") (pintype "passive"))
    )
    (net (code "46") (name "unconnected-(U101-DCD-Pad5)") (class "Default")
      (node (ref "U101") (pin "5") (pinfunction "DCD_5") (pintype "passive"))
    )
    (net (code "47") (name "unconnected-(U101-DISP_CLK-Pad11)") (class "Default")
      (node (ref "U101") (pin "11") (pinfunction "DISP_CLK_11") (pintype "passive"))
    )
    (net (code "48") (name "unconnected-(U101-DISP_CS-Pad14)") (class "Default")
      (node (ref "U101") (pin "14") (pinfunction "DISP_CS_14") (pintype "passive"))
    )
    (net (code "49") (name "unconnected-(U101-DISP_C{slash}D-Pad13)") (class "Default")
      (node (ref "U101") (pin "13") (pinfunction "DISP_C/D_13") (pintype "passive"))
    )
    (net (code "50") (name "unconnected-(U101-DISP_DATA-Pad12)") (class "Default")
      (node (ref "U101") (pin "12") (pinfunction "DISP_DATA_12") (pintype "passive"))
    )
    (net (code "51") (name "unconnected-(U101-DTR-Pad3)") (class "Default")
      (node (ref "U101") (pin "3") (pinfunction "DTR_3") (pintype "passive"))
    )
    (net (code "52") (name "unconnected-(U101-GPIO1{slash}KBR4-Pad40)") (class "Default")
      (node (ref "U101") (pin "40") (pinfunction "GPIO1/KBR4_40") (pintype "passive"))
    )
    (net (code "53") (name "unconnected-(U101-GPIO2{slash}KBR3-Pad41)") (class "Default")
      (node (ref "U101") (pin "41") (pinfunction "GPIO2/KBR3_41") (pintype "passive"))
    )
    (net (code "54") (name "unconnected-(U101-GPIO3{slash}KBR2-Pad42)") (class "Default")
      (node (ref "U101") (pin "42") (pinfunction "GPIO3/KBR2_42") (pintype "passive"))
    )
    (net (code "55") (name "unconnected-(U101-GPIO4{slash}KPR1-Pad43)") (class "Default")
      (node (ref "U101") (pin "43") (pinfunction "GPIO4/KPR1_43") (pintype "passive"))
    )
    (net (code "56") (name "unconnected-(U101-GPIO5{slash}KBR0-Pad44)") (class "Default")
      (node (ref "U101") (pin "44") (pinfunction "GPIO5/KBR0_44") (pintype "passive"))
    )
    (net (code "57") (name "unconnected-(U101-GPIO6{slash}KBC4-Pad47)") (class "Default")
      (node (ref "U101") (pin "47") (pinfunction "GPIO6/KBC4_47") (pintype "passive"))
    )
    (net (code "58") (name "unconnected-(U101-GPIO7{slash}KBC3-Pad48)") (class "Default")
      (node (ref "U101") (pin "48") (pinfunction "GPIO7/KBC3_48") (pintype "passive"))
    )
    (net (code "59") (name "unconnected-(U101-GPIO8{slash}KBC2-Pad49)") (class "Default")
      (node (ref "U101") (pin "49") (pinfunction "GPIO8/KBC2_49") (pintype "passive"))
    )
    (net (code "60") (name "unconnected-(U101-GPIO9{slash}KBC1-Pad50)") (class "Default")
      (node (ref "U101") (pin "50") (pinfunction "GPIO9/KBC1_50") (pintype "passive"))
    )
    (net (code "61") (name "unconnected-(U101-GPIO10-Pad51)") (class "Default")
      (node (ref "U101") (pin "51") (pinfunction "GPIO10_51") (pintype "passive"))
    )
    (net (code "62") (name "unconnected-(U101-GPIO11-Pad67)") (class "Default")
      (node (ref "U101") (pin "67") (pinfunction "GPIO11_67") (pintype "passive"))
    )
    (net (code "63") (name "unconnected-(U101-GPIO12-Pad68)") (class "Default")
      (node (ref "U101") (pin "68") (pinfunction "GPIO12_68") (pintype "passive"))
    )
    (net (code "64") (name "unconnected-(U101-LINEIN_L-Pad24)") (class "Default")
      (node (ref "U101") (pin "24") (pinfunction "LINEIN_L_24") (pintype "passive"))
    )
    (net (code "65") (name "unconnected-(U101-LINEIN_R-Pad23)") (class "Default")
      (node (ref "U101") (pin "23") (pinfunction "LINEIN_R_23") (pintype "passive"))
    )
    (net (code "66") (name "unconnected-(U101-MIC_N-Pad20)") (class "Default")
      (node (ref "U101") (pin "20") (pinfunction "MIC_N_20") (pintype "passive"))
    )
    (net (code "67") (name "unconnected-(U101-MIC_P-Pad19)") (class "Default")
      (node (ref "U101") (pin "19") (pinfunction "MIC_P_19") (pintype "passive"))
    )
    (net (code "68") (name "unconnected-(U101-NC-Pad2)") (class "Default")
      (node (ref "U101") (pin "2") (pinfunction "NC_2") (pintype "passive"))
    )
    (net (code "69") (name "unconnected-(U101-NC-Pad6)") (class "Default")
      (node (ref "U101") (pin "6") (pinfunction "NC_6") (pintype "passive"))
    )
    (net (code "70") (name "unconnected-(U101-PWM1-Pad35)") (class "Default")
      (node (ref "U101") (pin "35") (pinfunction "PWM1_35") (pintype "passive"))
    )
    (net (code "71") (name "unconnected-(U101-PWM2-Pad36)") (class "Default")
      (node (ref "U101") (pin "36") (pinfunction "PWM2_36") (pintype "passive"))
    )
    (net (code "72") (name "unconnected-(U101-RTS-Pad8)") (class "Default")
      (node (ref "U101") (pin "8") (pinfunction "RTS_8") (pintype "passive"))
    )
    (net (code "73") (name "unconnected-(U101-SCL-Pad38)") (class "Default")
      (node (ref "U101") (pin "38") (pinfunction "SCL_38") (pintype "passive"))
    )
    (net (code "74") (name "unconnected-(U101-SDA-Pad37)") (class "Default")
      (node (ref "U101") (pin "37") (pinfunction "SDA_37") (pintype "passive"))
    )
    (net (code "75") (name "unconnected-(U101-SIM_PRESENCE-Pad34)") (class "Default")
      (node (ref "U101") (pin "34") (pinfunction "SIM_PRESENCE_34") (pintype "passive"))
    )
    (net (code "76") (name "unconnected-(U101-SPK_N-Pad22)") (class "Default")
      (node (ref "U101") (pin "22") (pinfunction "SPK_N_22") (pintype "passive"))
    )
    (net (code "77") (name "unconnected-(U101-SPK_P-Pad21)") (class "Default")
      (node (ref "U101") (pin "21") (pinfunction "SPK_P_21") (pintype "passive"))
    )
    (net (code "78") (name "unconnected-(U102-Pad1)") (class "Default")
      (node (ref "U102") (pin "1") (pintype "passive"))
    )
    (net (code "79") (name "unconnected-(U102-Pad8)") (class "Default")
      (node (ref "U102") (pin "8") (pinfunction "8_8") (pintype "passive"))
    )
    (net (code "80") (name "unconnected-(U102-VPP-Pad6)") (class "Default")
      (node (ref "U102") (pin "6") (pinfunction "VPP_6") (pintype "passive"))
    )
    (net (code "81") (name "unconnected-(VD101-Pad5)") (class "Default")
      (node (ref "VD101") (pin "5") (pinfunction "5_5") (pintype "passive"))
    )
  )
)
